# cong_tac_wifi_TUYA.net
KiCad netlist of a schematic drawn in Altium Designer
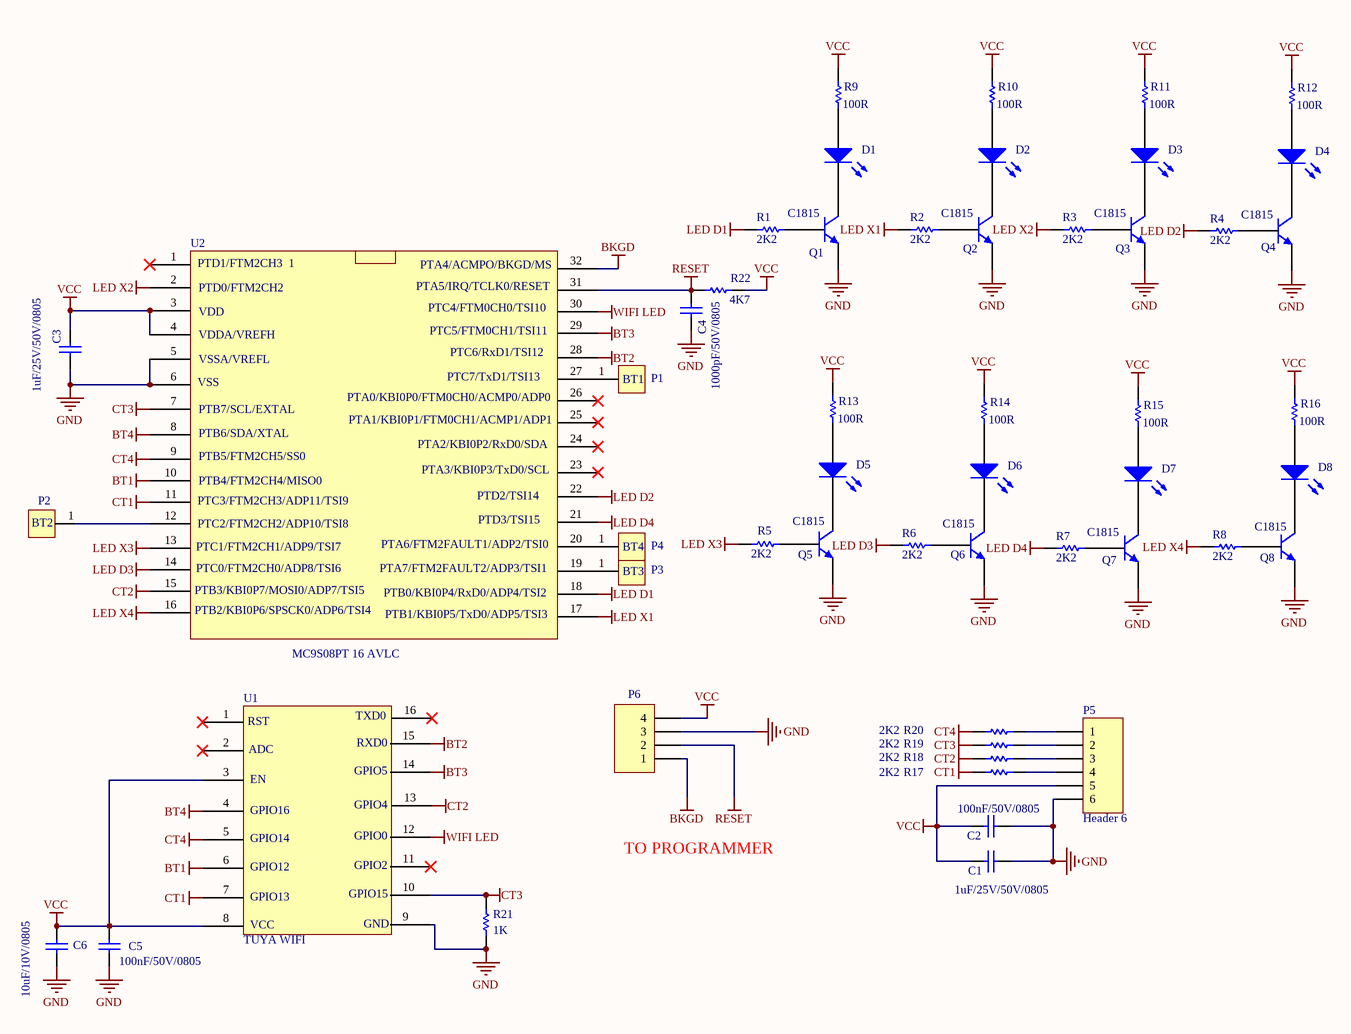
[diagram p0: cong tac wifi TUYA.SchDoc]

(export (version "E")
  (design (tool "Eeschema 10.0.6"))
  (components
    (comp (ref "C1")
      (value "1uF/25V/50V/0805")
      (footprint "tu 0805")
      (description "Capacitor")
      (libsource (lib "Miscellaneous Devices") (part "Cap"))
    )
    (comp (ref "C2")
      (value "100nF/50V/0805")
      (footprint "tu 0805")
      (description "Capacitor")
      (libsource (lib "Miscellaneous Devices") (part "Cap"))
    )
    (comp (ref "C3")
      (value "1uF/25V/50V/0805")
      (footprint "tu 0805")
      (description "Capacitor")
      (libsource (lib "Miscellaneous Devices") (part "Cap"))
    )
    (comp (ref "C4")
      (value "1000pF/50V/0805")
      (footprint "tu 0805")
      (description "Capacitor")
      (libsource (lib "Miscellaneous Devices") (part "Cap"))
    )
    (comp (ref "C5")
      (value "100nF/50V/0805")
      (footprint "tu 0805")
      (description "Capacitor")
      (libsource (lib "Miscellaneous Devices") (part "Cap"))
    )
    (comp (ref "C6")
      (value "10uF/10V/0805")
      (footprint "tu 0805")
      (description "Capacitor")
      (libsource (lib "Miscellaneous Devices") (part "Cap"))
    )
    (comp (ref "D1")
      (value "~")
      (footprint "LED 0805")
      (description "Typical INFRARED GaAs LED")
      (libsource (lib "Miscellaneous Devices") (part "LED0"))
    )
    (comp (ref "D2")
      (value "~")
      (footprint "LED 0805")
      (description "Typical INFRARED GaAs LED")
      (libsource (lib "Miscellaneous Devices") (part "LED0"))
    )
    (comp (ref "D3")
      (value "~")
      (footprint "LED 0805")
      (description "Typical INFRARED GaAs LED")
      (libsource (lib "Miscellaneous Devices") (part "LED0"))
    )
    (comp (ref "D4")
      (value "~")
      (footprint "LED 0805")
      (description "Typical INFRARED GaAs LED")
      (libsource (lib "Miscellaneous Devices") (part "LED0"))
    )
    (comp (ref "D5")
      (value "~")
      (footprint "LED 0805")
      (description "Typical INFRARED GaAs LED")
      (libsource (lib "Miscellaneous Devices") (part "LED0"))
    )
    (comp (ref "D6")
      (value "~")
      (footprint "LED 0805")
      (description "Typical INFRARED GaAs LED")
      (libsource (lib "Miscellaneous Devices") (part "LED0"))
    )
    (comp (ref "D7")
      (value "~")
      (footprint "LED 0805")
      (description "Typical INFRARED GaAs LED")
      (libsource (lib "Miscellaneous Devices") (part "LED0"))
    )
    (comp (ref "D8")
      (value "~")
      (footprint "LED 0805")
      (description "Typical INFRARED GaAs LED")
      (libsource (lib "Miscellaneous Devices") (part "LED0"))
    )
    (comp (ref "P1") (value "BT1") (footprint "jum don") (libsource (lib "Long") (part "Header 1")))
    (comp (ref "P2") (value "BT2") (footprint "jum don") (libsource (lib "") (part "Header 1_1")))
    (comp (ref "P3") (value "BT3") (footprint "jum don") (libsource (lib "Long") (part "Header 1")))
    (comp (ref "P4") (value "BT4") (footprint "jum don") (libsource (lib "Long") (part "Header 1")))
    (comp (ref "P5")
      (value "Header 6")
      (footprint "Jum 6 nam")
      (description "Header, 6-Pin")
      (libsource (lib "Miscellaneous Connectors") (part "Header 6"))
    )
    (comp (ref "P6")
      (value "~")
      (footprint "Jum 4 nho")
      (description "Header, 4-Pin")
      (libsource (lib "Miscellaneous Connectors") (part "Header 4"))
    )
    (comp (ref "Q1")
      (value "C1815")
      (footprint "C1815SMD")
      (description "NPN Bipolar Transistor")
      (libsource (lib "Miscellaneous Devices") (part "npn"))
    )
    (comp (ref "Q2")
      (value "C1815")
      (footprint "C1815SMD")
      (description "NPN Bipolar Transistor")
      (libsource (lib "Miscellaneous Devices") (part "npn"))
    )
    (comp (ref "Q3")
      (value "C1815")
      (footprint "C1815SMD")
      (description "NPN Bipolar Transistor")
      (libsource (lib "Miscellaneous Devices") (part "npn"))
    )
    (comp (ref "Q4")
      (value "C1815")
      (footprint "C1815SMD")
      (description "NPN Bipolar Transistor")
      (libsource (lib "Miscellaneous Devices") (part "npn"))
    )
    (comp (ref "Q5")
      (value "C1815")
      (footprint "C1815SMD")
      (description "NPN Bipolar Transistor")
      (libsource (lib "Miscellaneous Devices") (part "npn"))
    )
    (comp (ref "Q6")
      (value "C1815")
      (footprint "C1815SMD")
      (description "NPN Bipolar Transistor")
      (libsource (lib "Miscellaneous Devices") (part "npn"))
    )
    (comp (ref "Q7")
      (value "C1815")
      (footprint "C1815SMD")
      (description "NPN Bipolar Transistor")
      (libsource (lib "Miscellaneous Devices") (part "npn"))
    )
    (comp (ref "Q8")
      (value "C1815")
      (footprint "C1815SMD")
      (description "NPN Bipolar Transistor")
      (libsource (lib "Miscellaneous Devices") (part "npn"))
    )
    (comp (ref "R1")
      (value "2K2")
      (footprint "R0805")
      (description "Resistor")
      (libsource (lib "Miscellaneous Devices") (part "Res"))
    )
    (comp (ref "R2")
      (value "2K2")
      (footprint "R0805")
      (description "Resistor")
      (libsource (lib "Miscellaneous Devices") (part "Res"))
    )
    (comp (ref "R3")
      (value "2K2")
      (footprint "R0805")
      (description "Resistor")
      (libsource (lib "Miscellaneous Devices") (part "Res"))
    )
    (comp (ref "R4")
      (value "2K2")
      (footprint "R0805")
      (description "Resistor")
      (libsource (lib "Miscellaneous Devices") (part "Res"))
    )
    (comp (ref "R5")
      (value "2K2")
      (footprint "R0805")
      (description "Resistor")
      (libsource (lib "Miscellaneous Devices") (part "Res"))
    )
    (comp (ref "R6")
      (value "2K2")
      (footprint "R0805")
      (description "Resistor")
      (libsource (lib "Miscellaneous Devices") (part "Res"))
    )
    (comp (ref "R7")
      (value "2K2")
      (footprint "R0805")
      (description "Resistor")
      (libsource (lib "Miscellaneous Devices") (part "Res"))
    )
    (comp (ref "R8")
      (value "2K2")
      (footprint "R0805")
      (description "Resistor")
      (libsource (lib "Miscellaneous Devices") (part "Res"))
    )
    (comp (ref "R9")
      (value "100R")
      (footprint "R0805")
      (description "Resistor")
      (libsource (lib "Miscellaneous Devices") (part "Res"))
    )
    (comp (ref "R10")
      (value "100R")
      (footprint "R0805")
      (description "Resistor")
      (libsource (lib "Miscellaneous Devices") (part "Res"))
    )
    (comp (ref "R11")
      (value "100R")
      (footprint "R0805")
      (description "Resistor")
      (libsource (lib "Miscellaneous Devices") (part "Res"))
    )
    (comp (ref "R12")
      (value "100R")
      (footprint "R0805")
      (description "Resistor")
      (libsource (lib "Miscellaneous Devices") (part "Res"))
    )
    (comp (ref "R13")
      (value "100R")
      (footprint "R0805")
      (description "Resistor")
      (libsource (lib "Miscellaneous Devices") (part "Res"))
    )
    (comp (ref "R14")
      (value "100R")
      (footprint "R0805")
      (description "Resistor")
      (libsource (lib "Miscellaneous Devices") (part "Res"))
    )
    (comp (ref "R15")
      (value "100R")
      (footprint "R0805")
      (description "Resistor")
      (libsource (lib "Miscellaneous Devices") (part "Res"))
    )
    (comp (ref "R16")
      (value "100R")
      (footprint "R0805")
      (description "Resistor")
      (libsource (lib "Miscellaneous Devices") (part "Res"))
    )
    (comp (ref "R17")
      (value "2K2")
      (footprint "R0805")
      (description "Resistor")
      (libsource (lib "Miscellaneous Devices") (part "Res"))
    )
    (comp (ref "R18")
      (value "2K2")
      (footprint "R0805")
      (description "Resistor")
      (libsource (lib "Miscellaneous Devices") (part "Res"))
    )
    (comp (ref "R19")
      (value "2K2")
      (footprint "R0805")
      (description "Resistor")
      (libsource (lib "Miscellaneous Devices") (part "Res"))
    )
    (comp (ref "R20")
      (value "2K2")
      (footprint "R0805")
      (description "Resistor")
      (libsource (lib "Miscellaneous Devices") (part "Res"))
    )
    (comp (ref "R21")
      (value "1K")
      (footprint "R0805")
      (description "Resistor")
      (libsource (lib "Miscellaneous Devices") (part "Res"))
    )
    (comp (ref "R22")
      (value "4K7")
      (footprint "R0805")
      (description "Resistor")
      (libsource (lib "Miscellaneous Devices") (part "Res"))
    )
    (comp (ref "U1")
      (value "TUYA WIFI")
      (footprint "TUYA WIFI")
      (libsource (lib "TUYA WIFI") (part "TUYA WIFI"))
    )
    (comp (ref "U2")
      (value "MC9S08PT 16 AVLC")
      (footprint "M9S08PT 16AVLC")
      (libsource (lib "M9S08PT 16AVLC") (part "M9S08PT 16AVLC"))
    )
  )
  (nets
    (net (code "1") (name "BKGD") (class "Default")
      (node (ref "P6") (pin "1") (pinfunction "1_1") (pintype "passive"))
      (node (ref "U2") (pin "32") (pinfunction "32_32") (pintype "passive"))
    )
    (net (code "2") (name "BT1") (class "Default")
      (node (ref "U1") (pin "6") (pinfunction "6_6") (pintype "passive"))
      (node (ref "U2") (pin "10") (pinfunction "10_10") (pintype "passive"))
    )
    (net (code "3") (name "BT2") (class "Default")
      (node (ref "U1") (pin "15") (pinfunction "15_15") (pintype "passive"))
      (node (ref "U2") (pin "28") (pinfunction "28_28") (pintype "passive"))
    )
    (net (code "4") (name "BT3") (class "Default")
      (node (ref "U1") (pin "14") (pinfunction "14_14") (pintype "passive"))
      (node (ref "U2") (pin "29") (pinfunction "29_29") (pintype "passive"))
    )
    (net (code "5") (name "BT4") (class "Default")
      (node (ref "U1") (pin "4") (pinfunction "4_4") (pintype "passive"))
      (node (ref "U2") (pin "8") (pinfunction "8_8") (pintype "passive"))
    )
    (net (code "6") (name "CT1") (class "Default")
      (node (ref "R17") (pin "2") (pinfunction "2_2") (pintype "passive"))
      (node (ref "U1") (pin "7") (pinfunction "7_7") (pintype "passive"))
      (node (ref "U2") (pin "11") (pinfunction "11_11") (pintype "passive"))
    )
    (net (code "7") (name "CT2") (class "Default")
      (node (ref "R18") (pin "2") (pinfunction "2_2") (pintype "passive"))
      (node (ref "U1") (pin "13") (pinfunction "13_13") (pintype "passive"))
      (node (ref "U2") (pin "15") (pinfunction "15_15") (pintype "passive"))
    )
    (net (code "8") (name "CT3") (class "Default")
      (node (ref "R19") (pin "2") (pinfunction "2_2") (pintype "passive"))
      (node (ref "R21") (pin "1") (pinfunction "1_1") (pintype "passive"))
      (node (ref "U1") (pin "10") (pinfunction "10_10") (pintype "passive"))
      (node (ref "U2") (pin "7") (pinfunction "7_7") (pintype "passive"))
    )
    (net (code "9") (name "CT4") (class "Default")
      (node (ref "R20") (pin "2") (pinfunction "2_2") (pintype "passive"))
      (node (ref "U1") (pin "5") (pinfunction "5_5") (pintype "passive"))
      (node (ref "U2") (pin "9") (pinfunction "9_9") (pintype "passive"))
    )
    (net (code "10") (name "GND") (class "Default")
      (node (ref "C1") (pin "1") (pinfunction "1_1") (pintype "passive"))
      (node (ref "C2") (pin "1") (pinfunction "1_1") (pintype "passive"))
      (node (ref "C3") (pin "2") (pinfunction "2_2") (pintype "passive"))
      (node (ref "C4") (pin "2") (pinfunction "2_2") (pintype "passive"))
      (node (ref "C5") (pin "2") (pinfunction "2_2") (pintype "passive"))
      (node (ref "C6") (pin "2") (pinfunction "2_2") (pintype "passive"))
      (node (ref "P5") (pin "6") (pinfunction "6_6") (pintype "passive"))
      (node (ref "P6") (pin "3") (pinfunction "3_3") (pintype "passive"))
      (node (ref "Q1") (pin "3") (pinfunction "E_3") (pintype "passive"))
      (node (ref "Q2") (pin "3") (pinfunction "E_3") (pintype "passive"))
      (node (ref "Q3") (pin "3") (pinfunction "E_3") (pintype "passive"))
      (node (ref "Q4") (pin "3") (pinfunction "E_3") (pintype "passive"))
      (node (ref "Q5") (pin "3") (pinfunction "E_3") (pintype "passive"))
      (node (ref "Q6") (pin "3") (pinfunction "E_3") (pintype "passive"))
      (node (ref "Q7") (pin "3") (pinfunction "E_3") (pintype "passive"))
      (node (ref "Q8") (pin "3") (pinfunction "E_3") (pintype "passive"))
      (node (ref "R21") (pin "2") (pinfunction "2_2") (pintype "passive"))
      (node (ref "U1") (pin "9") (pinfunction "9_9") (pintype "passive"))
      (node (ref "U2") (pin "5") (pinfunction "5_5") (pintype "passive"))
      (node (ref "U2") (pin "6") (pinfunction "6_6") (pintype "passive"))
    )
    (net (code "11") (name "LED D1") (class "Default")
      (node (ref "R1") (pin "2") (pinfunction "2_2") (pintype "passive"))
      (node (ref "U2") (pin "18") (pinfunction "18_18") (pintype "passive"))
    )
    (net (code "12") (name "LED D2") (class "Default")
      (node (ref "R4") (pin "2") (pinfunction "2_2") (pintype "passive"))
      (node (ref "U2") (pin "22") (pinfunction "22_22") (pintype "passive"))
    )
    (net (code "13") (name "LED D3") (class "Default")
      (node (ref "R6") (pin "2") (pinfunction "2_2") (pintype "passive"))
      (node (ref "U2") (pin "14") (pinfunction "14_14") (pintype "passive"))
    )
    (net (code "14") (name "LED D4") (class "Default")
      (node (ref "R7") (pin "2") (pinfunction "2_2") (pintype "passive"))
      (node (ref "U2") (pin "21") (pinfunction "21_21") (pintype "passive"))
    )
    (net (code "15") (name "LED X1") (class "Default")
      (node (ref "R2") (pin "2") (pinfunction "2_2") (pintype "passive"))
      (node (ref "U2") (pin "17") (pinfunction "17_17") (pintype "passive"))
    )
    (net (code "16") (name "LED X2") (class "Default")
      (node (ref "R3") (pin "2") (pinfunction "2_2") (pintype "passive"))
      (node (ref "U2") (pin "2") (pinfunction "2_2") (pintype "passive"))
    )
    (net (code "17") (name "LED X3") (class "Default")
      (node (ref "R5") (pin "2") (pinfunction "2_2") (pintype "passive"))
      (node (ref "U2") (pin "13") (pinfunction "13_13") (pintype "passive"))
    )
    (net (code "18") (name "LED X4") (class "Default")
      (node (ref "R8") (pin "2") (pinfunction "2_2") (pintype "passive"))
      (node (ref "U2") (pin "16") (pinfunction "16_16") (pintype "passive"))
    )
    (net (code "19") (name "Net-(D1-A)") (class "Default")
      (node (ref "D1") (pin "1") (pinfunction "A_1") (pintype "passive"))
      (node (ref "R9") (pin "2") (pinfunction "2_2") (pintype "passive"))
    )
    (net (code "20") (name "Net-(D1-K)") (class "Default")
      (node (ref "D1") (pin "2") (pinfunction "K_2") (pintype "passive"))
      (node (ref "Q1") (pin "1") (pinfunction "C_1") (pintype "passive"))
    )
    (net (code "21") (name "Net-(D2-A)") (class "Default")
      (node (ref "D2") (pin "1") (pinfunction "A_1") (pintype "passive"))
      (node (ref "R10") (pin "2") (pinfunction "2_2") (pintype "passive"))
    )
    (net (code "22") (name "Net-(D2-K)") (class "Default")
      (node (ref "D2") (pin "2") (pinfunction "K_2") (pintype "passive"))
      (node (ref "Q2") (pin "1") (pinfunction "C_1") (pintype "passive"))
    )
    (net (code "23") (name "Net-(D3-A)") (class "Default")
      (node (ref "D3") (pin "1") (pinfunction "A_1") (pintype "passive"))
      (node (ref "R11") (pin "2") (pinfunction "2_2") (pintype "passive"))
    )
    (net (code "24") (name "Net-(D3-K)") (class "Default")
      (node (ref "D3") (pin "2") (pinfunction "K_2") (pintype "passive"))
      (node (ref "Q3") (pin "1") (pinfunction "C_1") (pintype "passive"))
    )
    (net (code "25") (name "Net-(D4-A)") (class "Default")
      (node (ref "D4") (pin "1") (pinfunction "A_1") (pintype "passive"))
      (node (ref "R12") (pin "2") (pinfunction "2_2") (pintype "passive"))
    )
    (net (code "26") (name "Net-(D4-K)") (class "Default")
      (node (ref "D4") (pin "2") (pinfunction "K_2") (pintype "passive"))
      (node (ref "Q4") (pin "1") (pinfunction "C_1") (pintype "passive"))
    )
    (net (code "27") (name "Net-(D5-A)") (class "Default")
      (node (ref "D5") (pin "1") (pinfunction "A_1") (pintype "passive"))
      (node (ref "R13") (pin "2") (pinfunction "2_2") (pintype "passive"))
    )
    (net (code "28") (name "Net-(D5-K)") (class "Default")
      (node (ref "D5") (pin "2") (pinfunction "K_2") (pintype "passive"))
      (node (ref "Q5") (pin "1") (pinfunction "C_1") (pintype "passive"))
    )
    (net (code "29") (name "Net-(D6-A)") (class "Default")
      (node (ref "D6") (pin "1") (pinfunction "A_1") (pintype "passive"))
      (node (ref "R14") (pin "2") (pinfunction "2_2") (pintype "passive"))
    )
    (net (code "30") (name "Net-(D6-K)") (class "Default")
      (node (ref "D6") (pin "2") (pinfunction "K_2") (pintype "passive"))
      (node (ref "Q6") (pin "1") (pinfunction "C_1") (pintype "passive"))
    )
    (net (code "31") (name "Net-(D7-A)") (class "Default")
      (node (ref "D7") (pin "1") (pinfunction "A_1") (pintype "passive"))
      (node (ref "R15") (pin "2") (pinfunction "2_2") (pintype "passive"))
    )
    (net (code "32") (name "Net-(D7-K)") (class "Default")
      (node (ref "D7") (pin "2") (pinfunction "K_2") (pintype "passive"))
      (node (ref "Q7") (pin "1") (pinfunction "C_1") (pintype "passive"))
    )
    (net (code "33") (name "Net-(D8-A)") (class "Default")
      (node (ref "D8") (pin "1") (pinfunction "A_1") (pintype "passive"))
      (node (ref "R16") (pin "2") (pinfunction "2_2") (pintype "passive"))
    )
    (net (code "34") (name "Net-(D8-K)") (class "Default")
      (node (ref "D8") (pin "2") (pinfunction "K_2") (pintype "passive"))
      (node (ref "Q8") (pin "1") (pinfunction "C_1") (pintype "passive"))
    )
    (net (code "35") (name "Net-(P1-Pad1)") (class "Default")
      (node (ref "P1") (pin "1") (pinfunction "1_1") (pintype "passive"))
      (node (ref "U2") (pin "27") (pinfunction "27_27") (pintype "passive"))
    )
    (net (code "36") (name "Net-(P2-Pad1)") (class "Default")
      (node (ref "P2") (pin "1") (pinfunction "1_1") (pintype "passive"))
      (node (ref "U2") (pin "12") (pinfunction "12_12") (pintype "passive"))
    )
    (net (code "37") (name "Net-(P3-Pad1)") (class "Default")
      (node (ref "P3") (pin "1") (pinfunction "1_1") (pintype "passive"))
      (node (ref "U2") (pin "19") (pinfunction "19_19") (pintype "passive"))
    )
    (net (code "38") (name "Net-(P4-Pad1)") (class "Default")
      (node (ref "P4") (pin "1") (pinfunction "1_1") (pintype "passive"))
      (node (ref "U2") (pin "20") (pinfunction "20_20") (pintype "passive"))
    )
    (net (code "39") (name "Net-(P5-Pad1)") (class "Default")
      (node (ref "P5") (pin "1") (pinfunction "1_1") (pintype "passive"))
      (node (ref "R20") (pin "1") (pinfunction "1_1") (pintype "passive"))
    )
    (net (code "40") (name "Net-(P5-Pad2)") (class "Default")
      (node (ref "P5") (pin "2") (pinfunction "2_2") (pintype "passive"))
      (node (ref "R19") (pin "1") (pinfunction "1_1") (pintype "passive"))
    )
    (net (code "41") (name "Net-(P5-Pad3)") (class "Default")
      (node (ref "P5") (pin "3") (pinfunction "3_3") (pintype "passive"))
      (node (ref "R18") (pin "1") (pinfunction "1_1") (pintype "passive"))
    )
    (net (code "42") (name "Net-(P5-Pad4)") (class "Default")
      (node (ref "P5") (pin "4") (pinfunction "4_4") (pintype "passive"))
      (node (ref "R17") (pin "1") (pinfunction "1_1") (pintype "passive"))
    )
    (net (code "43") (name "Net-(Q1-B)") (class "Default")
      (node (ref "Q1") (pin "2") (pinfunction "B_2") (pintype "passive"))
      (node (ref "R1") (pin "1") (pinfunction "1_1") (pintype "passive"))
    )
    (net (code "44") (name "Net-(Q2-B)") (class "Default")
      (node (ref "Q2") (pin "2") (pinfunction "B_2") (pintype "passive"))
      (node (ref "R2") (pin "1") (pinfunction "1_1") (pintype "passive"))
    )
    (net (code "45") (name "Net-(Q3-B)") (class "Default")
      (node (ref "Q3") (pin "2") (pinfunction "B_2") (pintype "passive"))
      (node (ref "R3") (pin "1") (pinfunction "1_1") (pintype "passive"))
    )
    (net (code "46") (name "Net-(Q4-B)") (class "Default")
      (node (ref "Q4") (pin "2") (pinfunction "B_2") (pintype "passive"))
      (node (ref "R4") (pin "1") (pinfunction "1_1") (pintype "passive"))
    )
    (net (code "47") (name "Net-(Q5-B)") (class "Default")
      (node (ref "Q5") (pin "2") (pinfunction "B_2") (pintype "passive"))
      (node (ref "R5") (pin "1") (pinfunction "1_1") (pintype "passive"))
    )
    (net (code "48") (name "Net-(Q6-B)") (class "Default")
      (node (ref "Q6") (pin "2") (pinfunction "B_2") (pintype "passive"))
      (node (ref "R6") (pin "1") (pinfunction "1_1") (pintype "passive"))
    )
    (net (code "49") (name "Net-(Q7-B)") (class "Default")
      (node (ref "Q7") (pin "2") (pinfunction "B_2") (pintype "passive"))
      (node (ref "R7") (pin "1") (pinfunction "1_1") (pintype "passive"))
    )
    (net (code "50") (name "Net-(Q8-B)") (class "Default")
      (node (ref "Q8") (pin "2") (pinfunction "B_2") (pintype "passive"))
      (node (ref "R8") (pin "1") (pinfunction "1_1") (pintype "passive"))
    )
    (net (code "51") (name "RESET") (class "Default")
      (node (ref "C4") (pin "1") (pinfunction "1_1") (pintype "passive"))
      (node (ref "P6") (pin "2") (pinfunction "2_2") (pintype "passive"))
      (node (ref "R22") (pin "2") (pinfunction "2_2") (pintype "passive"))
      (node (ref "U2") (pin "31") (pinfunction "31_31") (pintype "passive"))
    )
    (net (code "52") (name "VCC") (class "Default")
      (node (ref "C1") (pin "2") (pinfunction "2_2") (pintype "passive"))
      (node (ref "C2") (pin "2") (pinfunction "2_2") (pintype "passive"))
      (node (ref "C3") (pin "1") (pinfunction "1_1") (pintype "passive"))
      (node (ref "C5") (pin "1") (pinfunction "1_1") (pintype "passive"))
      (node (ref "C6") (pin "1") (pinfunction "1_1") (pintype "passive"))
      (node (ref "P5") (pin "5") (pinfunction "5_5") (pintype "passive"))
      (node (ref "P6") (pin "4") (pinfunction "4_4") (pintype "passive"))
      (node (ref "R10") (pin "1") (pinfunction "1_1") (pintype "passive"))
      (node (ref "R11") (pin "1") (pinfunction "1_1") (pintype "passive"))
      (node (ref "R12") (pin "1") (pinfunction "1_1") (pintype "passive"))
      (node (ref "R13") (pin "1") (pinfunction "1_1") (pintype "passive"))
      (node (ref "R14") (pin "1") (pinfunction "1_1") (pintype "passive"))
      (node (ref "R15") (pin "1") (pinfunction "1_1") (pintype "passive"))
      (node (ref "R16") (pin "1") (pinfunction "1_1") (pintype "passive"))
      (node (ref "R22") (pin "1") (pinfunction "1_1") (pintype "passive"))
      (node (ref "R9") (pin "1") (pinfunction "1_1") (pintype "passive"))
      (node (ref "U1") (pin "3") (pinfunction "3_3") (pintype "passive"))
      (node (ref "U1") (pin "8") (pinfunction "8_8") (pintype "passive"))
      (node (ref "U2") (pin "3") (pinfunction "3_3") (pintype "passive"))
      (node (ref "U2") (pin "4") (pinfunction "4_4") (pintype "passive"))
    )
    (net (code "53") (name "WIFI LED") (class "Default")
      (node (ref "U1") (pin "12") (pinfunction "12_12") (pintype "passive"))
      (node (ref "U2") (pin "30") (pinfunction "30_30") (pintype "passive"))
    )
    (net (code "54") (name "unconnected-(U1-Pad1)") (class "Default")
      (node (ref "U1") (pin "1") (pinfunction "1_1") (pintype "passive+no_connect"))
    )
    (net (code "55") (name "unconnected-(U1-Pad2)") (class "Default")
      (node (ref "U1") (pin "2") (pinfunction "2_2") (pintype "passive+no_connect"))
    )
    (net (code "56") (name "unconnected-(U1-Pad11)") (class "Default")
      (node (ref "U1") (pin "11") (pinfunction "11_11") (pintype "passive+no_connect"))
    )
    (net (code "57") (name "unconnected-(U1-Pad16)") (class "Default")
      (node (ref "U1") (pin "16") (pinfunction "16_16") (pintype "passive+no_connect"))
    )
    (net (code "58") (name "unconnected-(U2-Pad1)") (class "Default")
      (node (ref "U2") (pin "1") (pinfunction "1_1") (pintype "passive+no_connect"))
    )
    (net (code "59") (name "unconnected-(U2-Pad23)") (class "Default")
      (node (ref "U2") (pin "23") (pinfunction "23_23") (pintype "passive+no_connect"))
    )
    (net (code "60") (name "unconnected-(U2-Pad24)") (class "Default")
      (node (ref "U2") (pin "24") (pinfunction "24_24") (pintype "passive+no_connect"))
    )
    (net (code "61") (name "unconnected-(U2-Pad25)") (class "Default")
      (node (ref "U2") (pin "25") (pinfunction "25_25") (pintype "passive+no_connect"))
    )
    (net (code "62") (name "unconnected-(U2-Pad26)") (class "Default")
      (node (ref "U2") (pin "26") (pinfunction "26_26") (pintype "passive+no_connect"))
    )
  )
)
